# PGTN021_octasource2a_controls.net
KiCad netlist of a schematic drawn in EAGLE
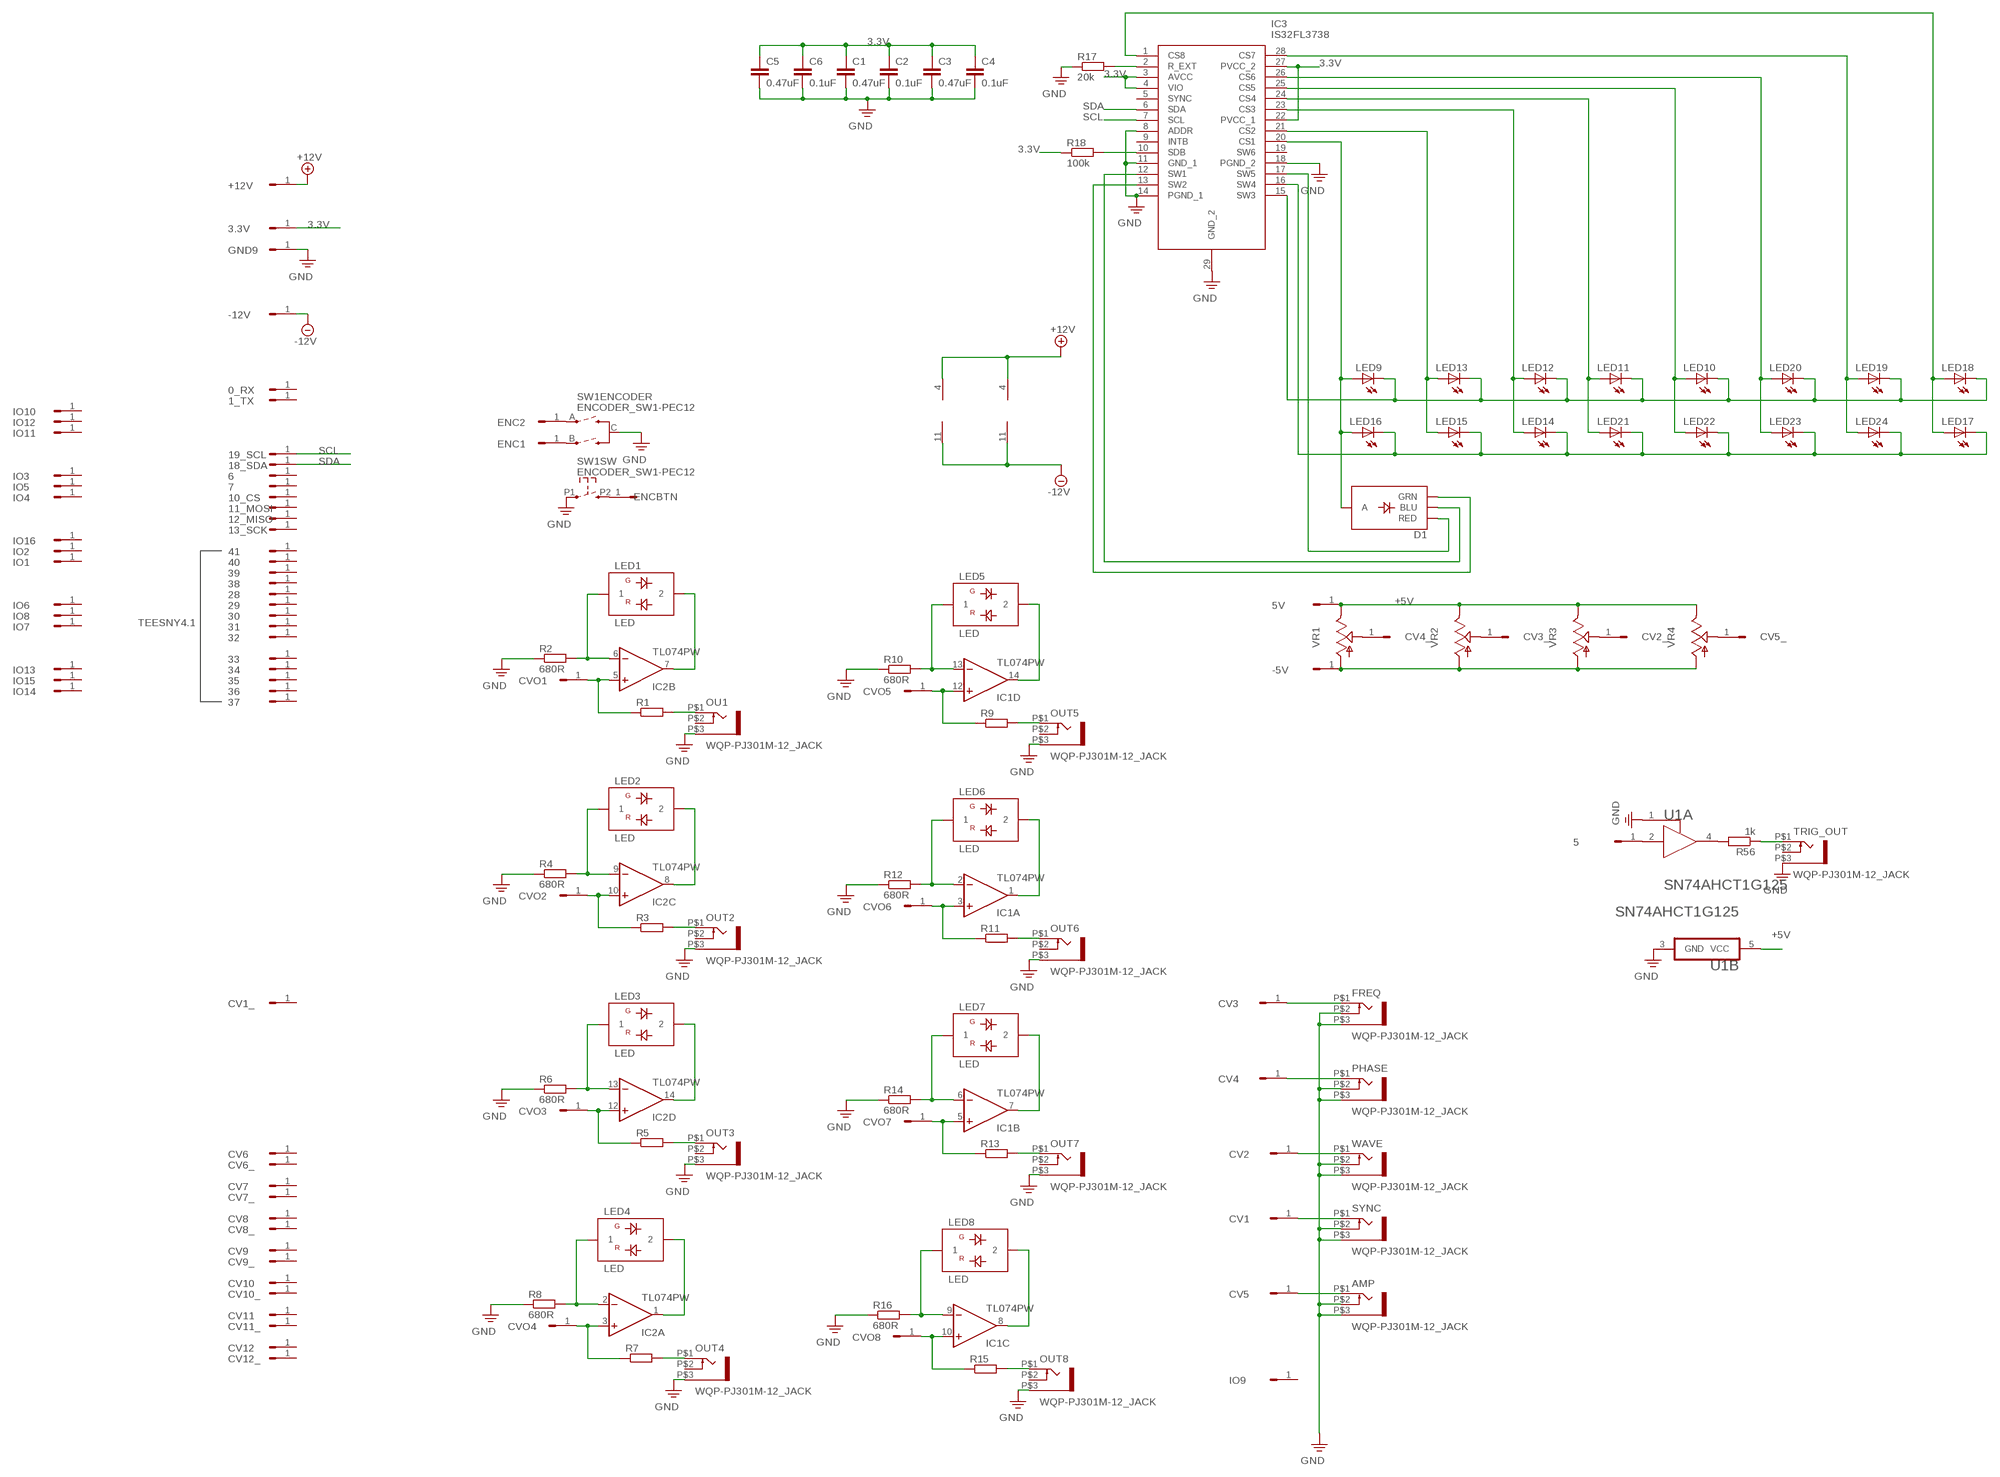
[diagram p0: schematic, sheet 1]

(export (version "E")
  (design (tool "Eeschema 10.0.6"))
  (components
    (comp (ref "+12V")
      (value "HEADER/MALE/01")
      (footprint "eagle-import:HEADER_MALE_01")
      (fields (field (name "SPICEPREFIX") "X"))
      (libsource (lib "eagle-import") (part "HEADER/MALE/01"))
    )
    (comp (ref "-5V")
      (value "HEADER/MALE/01")
      (footprint "eagle-import:HEADER_MALE_01")
      (fields (field (name "SPICEPREFIX") "X"))
      (libsource (lib "eagle-import") (part "HEADER/MALE/01"))
    )
    (comp (ref "-12V")
      (value "HEADER/MALE/01")
      (footprint "eagle-import:HEADER_MALE_01")
      (fields (field (name "SPICEPREFIX") "X"))
      (libsource (lib "eagle-import") (part "HEADER/MALE/01"))
    )
    (comp (ref "0_RX")
      (value "HEADER/MALE/01")
      (footprint "eagle-import:HEADER_MALE_01")
      (fields (field (name "SPICEPREFIX") "X"))
      (libsource (lib "eagle-import") (part "HEADER/MALE/01"))
    )
    (comp (ref "1_TX")
      (value "HEADER/MALE/01")
      (footprint "eagle-import:HEADER_MALE_01")
      (fields (field (name "SPICEPREFIX") "X"))
      (libsource (lib "eagle-import") (part "HEADER/MALE/01"))
    )
    (comp (ref "3.3V")
      (value "HEADER/MALE/01")
      (footprint "eagle-import:HEADER_MALE_01")
      (fields (field (name "SPICEPREFIX") "X"))
      (libsource (lib "eagle-import") (part "HEADER/MALE/01"))
    )
    (comp (ref "5")
      (value "HEADER/MALE/01")
      (footprint "eagle-import:HEADER_MALE_01")
      (fields (field (name "SPICEPREFIX") "X"))
      (libsource (lib "eagle-import") (part "HEADER/MALE/01"))
    )
    (comp (ref "5V")
      (value "HEADER/MALE/01")
      (footprint "eagle-import:HEADER_MALE_01")
      (fields (field (name "SPICEPREFIX") "X"))
      (libsource (lib "eagle-import") (part "HEADER/MALE/01"))
    )
    (comp (ref "6")
      (value "HEADER/MALE/01")
      (footprint "eagle-import:HEADER_MALE_01")
      (fields (field (name "SPICEPREFIX") "X"))
      (libsource (lib "eagle-import") (part "HEADER/MALE/01"))
    )
    (comp (ref "7")
      (value "HEADER/MALE/01")
      (footprint "eagle-import:HEADER_MALE_01")
      (fields (field (name "SPICEPREFIX") "X"))
      (libsource (lib "eagle-import") (part "HEADER/MALE/01"))
    )
    (comp (ref "10_CS")
      (value "HEADER/MALE/01")
      (footprint "eagle-import:HEADER_MALE_01")
      (fields (field (name "SPICEPREFIX") "X"))
      (libsource (lib "eagle-import") (part "HEADER/MALE/01"))
    )
    (comp (ref "11_MOSI")
      (value "HEADER/MALE/01")
      (footprint "eagle-import:HEADER_MALE_01")
      (fields (field (name "SPICEPREFIX") "X"))
      (libsource (lib "eagle-import") (part "HEADER/MALE/01"))
    )
    (comp (ref "12_MISO")
      (value "HEADER/MALE/01")
      (footprint "eagle-import:HEADER_MALE_01")
      (fields (field (name "SPICEPREFIX") "X"))
      (libsource (lib "eagle-import") (part "HEADER/MALE/01"))
    )
    (comp (ref "13_SCK")
      (value "HEADER/MALE/01")
      (footprint "eagle-import:HEADER_MALE_01")
      (fields (field (name "SPICEPREFIX") "X"))
      (libsource (lib "eagle-import") (part "HEADER/MALE/01"))
    )
    (comp (ref "18_SDA")
      (value "HEADER/MALE/01")
      (footprint "eagle-import:HEADER_MALE_01")
      (fields (field (name "SPICEPREFIX") "X"))
      (libsource (lib "eagle-import") (part "HEADER/MALE/01"))
    )
    (comp (ref "19_SCL")
      (value "HEADER/MALE/01")
      (footprint "eagle-import:HEADER_MALE_01")
      (fields (field (name "SPICEPREFIX") "X"))
      (libsource (lib "eagle-import") (part "HEADER/MALE/01"))
    )
    (comp (ref "28")
      (value "HEADER/MALE/01")
      (footprint "eagle-import:HEADER_MALE_01")
      (fields (field (name "SPICEPREFIX") "X"))
      (libsource (lib "eagle-import") (part "HEADER/MALE/01"))
    )
    (comp (ref "29")
      (value "HEADER/MALE/01")
      (footprint "eagle-import:HEADER_MALE_01")
      (fields (field (name "SPICEPREFIX") "X"))
      (libsource (lib "eagle-import") (part "HEADER/MALE/01"))
    )
    (comp (ref "30")
      (value "HEADER/MALE/01")
      (footprint "eagle-import:HEADER_MALE_01")
      (fields (field (name "SPICEPREFIX") "X"))
      (libsource (lib "eagle-import") (part "HEADER/MALE/01"))
    )
    (comp (ref "31")
      (value "HEADER/MALE/01")
      (footprint "eagle-import:HEADER_MALE_01")
      (fields (field (name "SPICEPREFIX") "X"))
      (libsource (lib "eagle-import") (part "HEADER/MALE/01"))
    )
    (comp (ref "32")
      (value "HEADER/MALE/01")
      (footprint "eagle-import:HEADER_MALE_01")
      (fields (field (name "SPICEPREFIX") "X"))
      (libsource (lib "eagle-import") (part "HEADER/MALE/01"))
    )
    (comp (ref "33")
      (value "HEADER/MALE/01")
      (footprint "eagle-import:HEADER_MALE_01")
      (fields (field (name "SPICEPREFIX") "X"))
      (libsource (lib "eagle-import") (part "HEADER/MALE/01"))
    )
    (comp (ref "34")
      (value "HEADER/MALE/01")
      (footprint "eagle-import:HEADER_MALE_01")
      (fields (field (name "SPICEPREFIX") "X"))
      (libsource (lib "eagle-import") (part "HEADER/MALE/01"))
    )
    (comp (ref "35")
      (value "HEADER/MALE/01")
      (footprint "eagle-import:HEADER_MALE_01")
      (fields (field (name "SPICEPREFIX") "X"))
      (libsource (lib "eagle-import") (part "HEADER/MALE/01"))
    )
    (comp (ref "36")
      (value "HEADER/MALE/01")
      (footprint "eagle-import:HEADER_MALE_01")
      (fields (field (name "SPICEPREFIX") "X"))
      (libsource (lib "eagle-import") (part "HEADER/MALE/01"))
    )
    (comp (ref "37")
      (value "HEADER/MALE/01")
      (footprint "eagle-import:HEADER_MALE_01")
      (fields (field (name "SPICEPREFIX") "X"))
      (libsource (lib "eagle-import") (part "HEADER/MALE/01"))
    )
    (comp (ref "38")
      (value "HEADER/MALE/01")
      (footprint "eagle-import:HEADER_MALE_01")
      (fields (field (name "SPICEPREFIX") "X"))
      (libsource (lib "eagle-import") (part "HEADER/MALE/01"))
    )
    (comp (ref "39")
      (value "HEADER/MALE/01")
      (footprint "eagle-import:HEADER_MALE_01")
      (fields (field (name "SPICEPREFIX") "X"))
      (libsource (lib "eagle-import") (part "HEADER/MALE/01"))
    )
    (comp (ref "40")
      (value "HEADER/MALE/01")
      (footprint "eagle-import:HEADER_MALE_01")
      (fields (field (name "SPICEPREFIX") "X"))
      (libsource (lib "eagle-import") (part "HEADER/MALE/01"))
    )
    (comp (ref "41")
      (value "HEADER/MALE/01")
      (footprint "eagle-import:HEADER_MALE_01")
      (fields (field (name "SPICEPREFIX") "X"))
      (libsource (lib "eagle-import") (part "HEADER/MALE/01"))
    )
    (comp (ref "AMP")
      (value "WQP-PJ301M-12_JACK")
      (footprint "eagle-import:WQP-PJ301M-12_JACK")
      (libsource (lib "eagle-import") (part "WQP-PJ301M-12_JACK"))
    )
    (comp (ref "C1")
      (value "0.47uF")
      (footprint "eagle-import:C0603")
      (libsource (lib "eagle-import") (part "CAPACITORC0603"))
    )
    (comp (ref "C2")
      (value "0.1uF")
      (footprint "eagle-import:C0603")
      (libsource (lib "eagle-import") (part "CAPACITORC0603"))
    )
    (comp (ref "C3")
      (value "0.47uF")
      (footprint "eagle-import:C0603")
      (libsource (lib "eagle-import") (part "CAPACITORC0603"))
    )
    (comp (ref "C4")
      (value "0.1uF")
      (footprint "eagle-import:C0603")
      (libsource (lib "eagle-import") (part "CAPACITORC0603"))
    )
    (comp (ref "C5")
      (value "0.47uF")
      (footprint "eagle-import:C0603")
      (libsource (lib "eagle-import") (part "CAPACITORC0603"))
    )
    (comp (ref "C6")
      (value "0.1uF")
      (footprint "eagle-import:C0603")
      (libsource (lib "eagle-import") (part "CAPACITORC0603"))
    )
    (comp (ref "CV1")
      (value "HEADER/MALE/01")
      (footprint "eagle-import:HEADER_MALE_01")
      (fields (field (name "SPICEPREFIX") "X"))
      (libsource (lib "eagle-import") (part "HEADER/MALE/01"))
    )
    (comp (ref "CV1_")
      (value "HEADER/MALE/01")
      (footprint "eagle-import:HEADER_MALE_01")
      (fields (field (name "SPICEPREFIX") "X"))
      (libsource (lib "eagle-import") (part "HEADER/MALE/01"))
    )
    (comp (ref "CV2")
      (value "HEADER/MALE/01")
      (footprint "eagle-import:HEADER_MALE_01")
      (fields (field (name "SPICEPREFIX") "X"))
      (libsource (lib "eagle-import") (part "HEADER/MALE/01"))
    )
    (comp (ref "CV2_")
      (value "HEADER/MALE/01")
      (footprint "eagle-import:HEADER_MALE_01")
      (fields (field (name "SPICEPREFIX") "X"))
      (libsource (lib "eagle-import") (part "HEADER/MALE/01"))
    )
    (comp (ref "CV3")
      (value "HEADER/MALE/01")
      (footprint "eagle-import:HEADER_MALE_01")
      (fields (field (name "SPICEPREFIX") "X"))
      (libsource (lib "eagle-import") (part "HEADER/MALE/01"))
    )
    (comp (ref "CV3_")
      (value "HEADER/MALE/01")
      (footprint "eagle-import:HEADER_MALE_01")
      (fields (field (name "SPICEPREFIX") "X"))
      (libsource (lib "eagle-import") (part "HEADER/MALE/01"))
    )
    (comp (ref "CV4")
      (value "HEADER/MALE/01")
      (footprint "eagle-import:HEADER_MALE_01")
      (fields (field (name "SPICEPREFIX") "X"))
      (libsource (lib "eagle-import") (part "HEADER/MALE/01"))
    )
    (comp (ref "CV4_")
      (value "HEADER/MALE/01")
      (footprint "eagle-import:HEADER_MALE_01")
      (fields (field (name "SPICEPREFIX") "X"))
      (libsource (lib "eagle-import") (part "HEADER/MALE/01"))
    )
    (comp (ref "CV5")
      (value "HEADER/MALE/01")
      (footprint "eagle-import:HEADER_MALE_01")
      (fields (field (name "SPICEPREFIX") "X"))
      (libsource (lib "eagle-import") (part "HEADER/MALE/01"))
    )
    (comp (ref "CV5_")
      (value "HEADER/MALE/01")
      (footprint "eagle-import:HEADER_MALE_01")
      (fields (field (name "SPICEPREFIX") "X"))
      (libsource (lib "eagle-import") (part "HEADER/MALE/01"))
    )
    (comp (ref "CV6")
      (value "HEADER/MALE/01")
      (footprint "eagle-import:HEADER_MALE_01")
      (fields (field (name "SPICEPREFIX") "X"))
      (libsource (lib "eagle-import") (part "HEADER/MALE/01"))
    )
    (comp (ref "CV6_")
      (value "HEADER/MALE/01")
      (footprint "eagle-import:HEADER_MALE_01")
      (fields (field (name "SPICEPREFIX") "X"))
      (libsource (lib "eagle-import") (part "HEADER/MALE/01"))
    )
    (comp (ref "CV7")
      (value "HEADER/MALE/01")
      (footprint "eagle-import:HEADER_MALE_01")
      (fields (field (name "SPICEPREFIX") "X"))
      (libsource (lib "eagle-import") (part "HEADER/MALE/01"))
    )
    (comp (ref "CV7_")
      (value "HEADER/MALE/01")
      (footprint "eagle-import:HEADER_MALE_01")
      (fields (field (name "SPICEPREFIX") "X"))
      (libsource (lib "eagle-import") (part "HEADER/MALE/01"))
    )
    (comp (ref "CV8")
      (value "HEADER/MALE/01")
      (footprint "eagle-import:HEADER_MALE_01")
      (fields (field (name "SPICEPREFIX") "X"))
      (libsource (lib "eagle-import") (part "HEADER/MALE/01"))
    )
    (comp (ref "CV8_")
      (value "HEADER/MALE/01")
      (footprint "eagle-import:HEADER_MALE_01")
      (fields (field (name "SPICEPREFIX") "X"))
      (libsource (lib "eagle-import") (part "HEADER/MALE/01"))
    )
    (comp (ref "CV9")
      (value "HEADER/MALE/01")
      (footprint "eagle-import:HEADER_MALE_01")
      (fields (field (name "SPICEPREFIX") "X"))
      (libsource (lib "eagle-import") (part "HEADER/MALE/01"))
    )
    (comp (ref "CV9_")
      (value "HEADER/MALE/01")
      (footprint "eagle-import:HEADER_MALE_01")
      (fields (field (name "SPICEPREFIX") "X"))
      (libsource (lib "eagle-import") (part "HEADER/MALE/01"))
    )
    (comp (ref "CV10")
      (value "HEADER/MALE/01")
      (footprint "eagle-import:HEADER_MALE_01")
      (fields (field (name "SPICEPREFIX") "X"))
      (libsource (lib "eagle-import") (part "HEADER/MALE/01"))
    )
    (comp (ref "CV10_")
      (value "HEADER/MALE/01")
      (footprint "eagle-import:HEADER_MALE_01")
      (fields (field (name "SPICEPREFIX") "X"))
      (libsource (lib "eagle-import") (part "HEADER/MALE/01"))
    )
    (comp (ref "CV11")
      (value "HEADER/MALE/01")
      (footprint "eagle-import:HEADER_MALE_01")
      (fields (field (name "SPICEPREFIX") "X"))
      (libsource (lib "eagle-import") (part "HEADER/MALE/01"))
    )
    (comp (ref "CV11_")
      (value "HEADER/MALE/01")
      (footprint "eagle-import:HEADER_MALE_01")
      (fields (field (name "SPICEPREFIX") "X"))
      (libsource (lib "eagle-import") (part "HEADER/MALE/01"))
    )
    (comp (ref "CV12")
      (value "HEADER/MALE/01")
      (footprint "eagle-import:HEADER_MALE_01")
      (fields (field (name "SPICEPREFIX") "X"))
      (libsource (lib "eagle-import") (part "HEADER/MALE/01"))
    )
    (comp (ref "CV12_")
      (value "HEADER/MALE/01")
      (footprint "eagle-import:HEADER_MALE_01")
      (fields (field (name "SPICEPREFIX") "X"))
      (libsource (lib "eagle-import") (part "HEADER/MALE/01"))
    )
    (comp (ref "CVO1")
      (value "HEADER/MALE/01")
      (footprint "eagle-import:HEADER_MALE_01")
      (fields (field (name "SPICEPREFIX") "X"))
      (libsource (lib "eagle-import") (part "HEADER/MALE/01"))
    )
    (comp (ref "CVO2")
      (value "HEADER/MALE/01")
      (footprint "eagle-import:HEADER_MALE_01")
      (fields (field (name "SPICEPREFIX") "X"))
      (libsource (lib "eagle-import") (part "HEADER/MALE/01"))
    )
    (comp (ref "CVO3")
      (value "HEADER/MALE/01")
      (footprint "eagle-import:HEADER_MALE_01")
      (fields (field (name "SPICEPREFIX") "X"))
      (libsource (lib "eagle-import") (part "HEADER/MALE/01"))
    )
    (comp (ref "CVO4")
      (value "HEADER/MALE/01")
      (footprint "eagle-import:HEADER_MALE_01")
      (fields (field (name "SPICEPREFIX") "X"))
      (libsource (lib "eagle-import") (part "HEADER/MALE/01"))
    )
    (comp (ref "CVO5")
      (value "HEADER/MALE/01")
      (footprint "eagle-import:HEADER_MALE_01")
      (fields (field (name "SPICEPREFIX") "X"))
      (libsource (lib "eagle-import") (part "HEADER/MALE/01"))
    )
    (comp (ref "CVO6")
      (value "HEADER/MALE/01")
      (footprint "eagle-import:HEADER_MALE_01")
      (fields (field (name "SPICEPREFIX") "X"))
      (libsource (lib "eagle-import") (part "HEADER/MALE/01"))
    )
    (comp (ref "CVO7")
      (value "HEADER/MALE/01")
      (footprint "eagle-import:HEADER_MALE_01")
      (fields (field (name "SPICEPREFIX") "X"))
      (libsource (lib "eagle-import") (part "HEADER/MALE/01"))
    )
    (comp (ref "CVO8")
      (value "HEADER/MALE/01")
      (footprint "eagle-import:HEADER_MALE_01")
      (fields (field (name "SPICEPREFIX") "X"))
      (libsource (lib "eagle-import") (part "HEADER/MALE/01"))
    )
    (comp (ref "D1")
      (value "LED-RGB-CADIALIGHT1210")
      (footprint "eagle-import:CHIPLED_1210")
      (libsource (lib "eagle-import") (part "LED-RGB-CADIALIGHT1210"))
    )
    (comp (ref "ENC1")
      (value "HEADER/MALE/01")
      (footprint "eagle-import:HEADER_MALE_01")
      (fields (field (name "SPICEPREFIX") "X"))
      (libsource (lib "eagle-import") (part "HEADER/MALE/01"))
    )
    (comp (ref "ENC2")
      (value "HEADER/MALE/01")
      (footprint "eagle-import:HEADER_MALE_01")
      (fields (field (name "SPICEPREFIX") "X"))
      (libsource (lib "eagle-import") (part "HEADER/MALE/01"))
    )
    (comp (ref "ENCBTN")
      (value "HEADER/MALE/01")
      (footprint "eagle-import:HEADER_MALE_01")
      (fields (field (name "SPICEPREFIX") "X"))
      (libsource (lib "eagle-import") (part "HEADER/MALE/01"))
    )
    (comp (ref "FREQ")
      (value "WQP-PJ301M-12_JACK")
      (footprint "eagle-import:WQP-PJ301M-12_JACK")
      (libsource (lib "eagle-import") (part "WQP-PJ301M-12_JACK"))
    )
    (comp (ref "GND9")
      (value "HEADER/MALE/01")
      (footprint "eagle-import:HEADER_MALE_01")
      (fields (field (name "SPICEPREFIX") "X"))
      (libsource (lib "eagle-import") (part "HEADER/MALE/01"))
    )
    (comp (ref "IC1")
      (value "TL074PW")
      (footprint "eagle-import:TSSOP14")
      (libsource (lib "eagle-import") (part "TL074PW"))
    )
    (comp (ref "IC2")
      (value "TL074PW")
      (footprint "eagle-import:TSSOP14")
      (libsource (lib "eagle-import") (part "TL074PW"))
    )
    (comp (ref "IC3")
      (value "IS32FL3738")
      (footprint "eagle-import:TSSOP29")
      (fields (field (name "MANUFACTURER_PART_NUMBER") "IS32FL3738-ZLA3-TR"))
      (libsource (lib "eagle-import") (part "IS32FL3738"))
    )
    (comp (ref "IO1")
      (value "HEADER/MALE/01")
      (footprint "eagle-import:HEADER_MALE_01")
      (fields (field (name "SPICEPREFIX") "X"))
      (libsource (lib "eagle-import") (part "HEADER/MALE/01"))
    )
    (comp (ref "IO2")
      (value "HEADER/MALE/01")
      (footprint "eagle-import:HEADER_MALE_01")
      (fields (field (name "SPICEPREFIX") "X"))
      (libsource (lib "eagle-import") (part "HEADER/MALE/01"))
    )
    (comp (ref "IO3")
      (value "HEADER/MALE/01")
      (footprint "eagle-import:HEADER_MALE_01")
      (fields (field (name "SPICEPREFIX") "X"))
      (libsource (lib "eagle-import") (part "HEADER/MALE/01"))
    )
    (comp (ref "IO4")
      (value "HEADER/MALE/01")
      (footprint "eagle-import:HEADER_MALE_01")
      (fields (field (name "SPICEPREFIX") "X"))
      (libsource (lib "eagle-import") (part "HEADER/MALE/01"))
    )
    (comp (ref "IO5")
      (value "HEADER/MALE/01")
      (footprint "eagle-import:HEADER_MALE_01")
      (fields (field (name "SPICEPREFIX") "X"))
      (libsource (lib "eagle-import") (part "HEADER/MALE/01"))
    )
    (comp (ref "IO6")
      (value "HEADER/MALE/01")
      (footprint "eagle-import:HEADER_MALE_01")
      (fields (field (name "SPICEPREFIX") "X"))
      (libsource (lib "eagle-import") (part "HEADER/MALE/01"))
    )
    (comp (ref "IO7")
      (value "HEADER/MALE/01")
      (footprint "eagle-import:HEADER_MALE_01")
      (fields (field (name "SPICEPREFIX") "X"))
      (libsource (lib "eagle-import") (part "HEADER/MALE/01"))
    )
    (comp (ref "IO8")
      (value "HEADER/MALE/01")
      (footprint "eagle-import:HEADER_MALE_01")
      (fields (field (name "SPICEPREFIX") "X"))
      (libsource (lib "eagle-import") (part "HEADER/MALE/01"))
    )
    (comp (ref "IO9")
      (value "HEADER/MALE/01")
      (footprint "eagle-import:HEADER_MALE_01")
      (fields (field (name "SPICEPREFIX") "X"))
      (libsource (lib "eagle-import") (part "HEADER/MALE/01"))
    )
    (comp (ref "IO10")
      (value "HEADER/MALE/01")
      (footprint "eagle-import:HEADER_MALE_01")
      (fields (field (name "SPICEPREFIX") "X"))
      (libsource (lib "eagle-import") (part "HEADER/MALE/01"))
    )
    (comp (ref "IO11")
      (value "HEADER/MALE/01")
      (footprint "eagle-import:HEADER_MALE_01")
      (fields (field (name "SPICEPREFIX") "X"))
      (libsource (lib "eagle-import") (part "HEADER/MALE/01"))
    )
    (comp (ref "IO12")
      (value "HEADER/MALE/01")
      (footprint "eagle-import:HEADER_MALE_01")
      (fields (field (name "SPICEPREFIX") "X"))
      (libsource (lib "eagle-import") (part "HEADER/MALE/01"))
    )
    (comp (ref "IO13")
      (value "HEADER/MALE/01")
      (footprint "eagle-import:HEADER_MALE_01")
      (fields (field (name "SPICEPREFIX") "X"))
      (libsource (lib "eagle-import") (part "HEADER/MALE/01"))
    )
    (comp (ref "IO14")
      (value "HEADER/MALE/01")
      (footprint "eagle-import:HEADER_MALE_01")
      (fields (field (name "SPICEPREFIX") "X"))
      (libsource (lib "eagle-import") (part "HEADER/MALE/01"))
    )
    (comp (ref "IO15")
      (value "HEADER/MALE/01")
      (footprint "eagle-import:HEADER_MALE_01")
      (fields (field (name "SPICEPREFIX") "X"))
      (libsource (lib "eagle-import") (part "HEADER/MALE/01"))
    )
    (comp (ref "IO16")
      (value "HEADER/MALE/01")
      (footprint "eagle-import:HEADER_MALE_01")
      (fields (field (name "SPICEPREFIX") "X"))
      (libsource (lib "eagle-import") (part "HEADER/MALE/01"))
    )
    (comp (ref "LED1")
      (value "LED")
      (footprint "eagle-import:OG-LEDS_LED3MM")
      (libsource (lib "eagle-import") (part "LED-BICOLOR-SHARED"))
    )
    (comp (ref "LED2")
      (value "LED")
      (footprint "eagle-import:OG-LEDS_LED3MM")
      (libsource (lib "eagle-import") (part "LED-BICOLOR-SHARED"))
    )
    (comp (ref "LED3")
      (value "LED")
      (footprint "eagle-import:OG-LEDS_LED3MM")
      (libsource (lib "eagle-import") (part "LED-BICOLOR-SHARED"))
    )
    (comp (ref "LED4")
      (value "LED")
      (footprint "eagle-import:OG-LEDS_LED3MM")
      (libsource (lib "eagle-import") (part "LED-BICOLOR-SHARED"))
    )
    (comp (ref "LED5")
      (value "LED")
      (footprint "eagle-import:OG-LEDS_LED3MM")
      (libsource (lib "eagle-import") (part "LED-BICOLOR-SHARED"))
    )
    (comp (ref "LED6")
      (value "LED")
      (footprint "eagle-import:OG-LEDS_LED3MM")
      (libsource (lib "eagle-import") (part "LED-BICOLOR-SHARED"))
    )
    (comp (ref "LED7")
      (value "LED")
      (footprint "eagle-import:OG-LEDS_LED3MM")
      (libsource (lib "eagle-import") (part "LED-BICOLOR-SHARED"))
    )
    (comp (ref "LED8")
      (value "LED")
      (footprint "eagle-import:OG-LEDS_LED3MM")
      (libsource (lib "eagle-import") (part "LED-BICOLOR-SHARED"))
    )
    (comp (ref "LED9")
      (value "LEDCHIPLED_0805")
      (footprint "eagle-import:CHIPLED_0805")
      (libsource (lib "eagle-import") (part "LEDCHIPLED_0805"))
    )
    (comp (ref "LED10")
      (value "LEDCHIPLED_0805")
      (footprint "eagle-import:CHIPLED_0805")
      (libsource (lib "eagle-import") (part "LEDCHIPLED_0805"))
    )
    (comp (ref "LED11")
      (value "LEDCHIPLED_0805")
      (footprint "eagle-import:CHIPLED_0805")
      (libsource (lib "eagle-import") (part "LEDCHIPLED_0805"))
    )
    (comp (ref "LED12")
      (value "LEDCHIPLED_0805")
      (footprint "eagle-import:CHIPLED_0805")
      (libsource (lib "eagle-import") (part "LEDCHIPLED_0805"))
    )
    (comp (ref "LED13")
      (value "LEDCHIPLED_0805")
      (footprint "eagle-import:CHIPLED_0805")
      (libsource (lib "eagle-import") (part "LEDCHIPLED_0805"))
    )
    (comp (ref "LED14")
      (value "LEDCHIPLED_0805")
      (footprint "eagle-import:CHIPLED_0805")
      (libsource (lib "eagle-import") (part "LEDCHIPLED_0805"))
    )
    (comp (ref "LED15")
      (value "LEDCHIPLED_0805")
      (footprint "eagle-import:CHIPLED_0805")
      (libsource (lib "eagle-import") (part "LEDCHIPLED_0805"))
    )
    (comp (ref "LED16")
      (value "LEDCHIPLED_0805")
      (footprint "eagle-import:CHIPLED_0805")
      (libsource (lib "eagle-import") (part "LEDCHIPLED_0805"))
    )
    (comp (ref "LED17")
      (value "LEDCHIPLED_0805")
      (footprint "eagle-import:CHIPLED_0805")
      (libsource (lib "eagle-import") (part "LEDCHIPLED_0805"))
    )
    (comp (ref "LED18")
      (value "LEDCHIPLED_0805")
      (footprint "eagle-import:CHIPLED_0805")
      (libsource (lib "eagle-import") (part "LEDCHIPLED_0805"))
    )
    (comp (ref "LED19")
      (value "LEDCHIPLED_0805")
      (footprint "eagle-import:CHIPLED_0805")
      (libsource (lib "eagle-import") (part "LEDCHIPLED_0805"))
    )
    (comp (ref "LED20")
      (value "LEDCHIPLED_0805")
      (footprint "eagle-import:CHIPLED_0805")
      (libsource (lib "eagle-import") (part "LEDCHIPLED_0805"))
    )
    (comp (ref "LED21")
      (value "LEDCHIPLED_0805")
      (footprint "eagle-import:CHIPLED_0805")
      (libsource (lib "eagle-import") (part "LEDCHIPLED_0805"))
    )
    (comp (ref "LED22")
      (value "LEDCHIPLED_0805")
      (footprint "eagle-import:CHIPLED_0805")
      (libsource (lib "eagle-import") (part "LEDCHIPLED_0805"))
    )
    (comp (ref "LED23")
      (value "LEDCHIPLED_0805")
      (footprint "eagle-import:CHIPLED_0805")
      (libsource (lib "eagle-import") (part "LEDCHIPLED_0805"))
    )
    (comp (ref "LED24")
      (value "LEDCHIPLED_0805")
      (footprint "eagle-import:CHIPLED_0805")
      (libsource (lib "eagle-import") (part "LEDCHIPLED_0805"))
    )
    (comp (ref "OU1")
      (value "WQP-PJ301M-12_JACK")
      (footprint "eagle-import:WQP-PJ301M-12_JACK")
      (libsource (lib "eagle-import") (part "WQP-PJ301M-12_JACK"))
    )
    (comp (ref "OUT2")
      (value "WQP-PJ301M-12_JACK")
      (footprint "eagle-import:WQP-PJ301M-12_JACK")
      (libsource (lib "eagle-import") (part "WQP-PJ301M-12_JACK"))
    )
    (comp (ref "OUT3")
      (value "WQP-PJ301M-12_JACK")
      (footprint "eagle-import:WQP-PJ301M-12_JACK")
      (libsource (lib "eagle-import") (part "WQP-PJ301M-12_JACK"))
    )
    (comp (ref "OUT4")
      (value "WQP-PJ301M-12_JACK")
      (footprint "eagle-import:WQP-PJ301M-12_JACK")
      (libsource (lib "eagle-import") (part "WQP-PJ301M-12_JACK"))
    )
    (comp (ref "OUT5")
      (value "WQP-PJ301M-12_JACK")
      (footprint "eagle-import:WQP-PJ301M-12_JACK")
      (libsource (lib "eagle-import") (part "WQP-PJ301M-12_JACK"))
    )
    (comp (ref "OUT6")
      (value "WQP-PJ301M-12_JACK")
      (footprint "eagle-import:WQP-PJ301M-12_JACK")
      (libsource (lib "eagle-import") (part "WQP-PJ301M-12_JACK"))
    )
    (comp (ref "OUT7")
      (value "WQP-PJ301M-12_JACK")
      (footprint "eagle-import:WQP-PJ301M-12_JACK")
      (libsource (lib "eagle-import") (part "WQP-PJ301M-12_JACK"))
    )
    (comp (ref "OUT8")
      (value "WQP-PJ301M-12_JACK")
      (footprint "eagle-import:WQP-PJ301M-12_JACK")
      (libsource (lib "eagle-import") (part "WQP-PJ301M-12_JACK"))
    )
    (comp (ref "PHASE")
      (value "WQP-PJ301M-12_JACK")
      (footprint "eagle-import:WQP-PJ301M-12_JACK")
      (libsource (lib "eagle-import") (part "WQP-PJ301M-12_JACK"))
    )
    (comp (ref "R1")
      (value "RESISTOR")
      (footprint "eagle-import:R0603")
      (libsource (lib "eagle-import") (part "RESISTOR"))
    )
    (comp (ref "R2")
      (value "680R")
      (footprint "eagle-import:R0603")
      (libsource (lib "eagle-import") (part "RESISTOR"))
    )
    (comp (ref "R3")
      (value "RESISTOR")
      (footprint "eagle-import:R0603")
      (libsource (lib "eagle-import") (part "RESISTOR"))
    )
    (comp (ref "R4")
      (value "680R")
      (footprint "eagle-import:R0603")
      (libsource (lib "eagle-import") (part "RESISTOR"))
    )
    (comp (ref "R5")
      (value "RESISTOR")
      (footprint "eagle-import:R0603")
      (libsource (lib "eagle-import") (part "RESISTOR"))
    )
    (comp (ref "R6")
      (value "680R")
      (footprint "eagle-import:R0603")
      (libsource (lib "eagle-import") (part "RESISTOR"))
    )
    (comp (ref "R7")
      (value "RESISTOR")
      (footprint "eagle-import:R0603")
      (libsource (lib "eagle-import") (part "RESISTOR"))
    )
    (comp (ref "R8")
      (value "680R")
      (footprint "eagle-import:R0603")
      (libsource (lib "eagle-import") (part "RESISTOR"))
    )
    (comp (ref "R9")
      (value "RESISTOR")
      (footprint "eagle-import:R0603")
      (libsource (lib "eagle-import") (part "RESISTOR"))
    )
    (comp (ref "R10")
      (value "680R")
      (footprint "eagle-import:R0603")
      (libsource (lib "eagle-import") (part "RESISTOR"))
    )
    (comp (ref "R11")
      (value "RESISTOR")
      (footprint "eagle-import:R0603")
      (libsource (lib "eagle-import") (part "RESISTOR"))
    )
    (comp (ref "R12")
      (value "680R")
      (footprint "eagle-import:R0603")
      (libsource (lib "eagle-import") (part "RESISTOR"))
    )
    (comp (ref "R13")
      (value "RESISTOR")
      (footprint "eagle-import:R0603")
      (libsource (lib "eagle-import") (part "RESISTOR"))
    )
    (comp (ref "R14")
      (value "680R")
      (footprint "eagle-import:R0603")
      (libsource (lib "eagle-import") (part "RESISTOR"))
    )
    (comp (ref "R15")
      (value "RESISTOR")
      (footprint "eagle-import:R0603")
      (libsource (lib "eagle-import") (part "RESISTOR"))
    )
    (comp (ref "R16")
      (value "680R")
      (footprint "eagle-import:R0603")
      (libsource (lib "eagle-import") (part "RESISTOR"))
    )
    (comp (ref "R17")
      (value "20k")
      (footprint "eagle-import:R0603")
      (libsource (lib "eagle-import") (part "RESISTOR"))
    )
    (comp (ref "R18")
      (value "100k")
      (footprint "eagle-import:R0603")
      (libsource (lib "eagle-import") (part "RESISTOR"))
    )
    (comp (ref "R56")
      (value "1k")
      (footprint "eagle-import:R0603")
      (libsource (lib "eagle-import") (part "RESISTOR"))
    )
    (comp (ref "SW1")
      (value "ENCODER_SW1-PEC12")
      (footprint "eagle-import:PEC12_INCREMENTAL_ENCODER")
      (libsource (lib "eagle-import") (part "ENCODER_SW1-PEC12"))
    )
    (comp (ref "SYNC")
      (value "WQP-PJ301M-12_JACK")
      (footprint "eagle-import:WQP-PJ301M-12_JACK")
      (libsource (lib "eagle-import") (part "WQP-PJ301M-12_JACK"))
    )
    (comp (ref "TRIG_OUT")
      (value "WQP-PJ301M-12_JACK")
      (footprint "eagle-import:WQP-PJ301M-12_JACK")
      (libsource (lib "eagle-import") (part "WQP-PJ301M-12_JACK"))
    )
    (comp (ref "U1")
      (value "74AHCT1G125\"")
      (footprint "eagle-import:74AHCT1G125")
      (fields (field (name "MF") "Texas Instruments") (field (name "MPN") "SN74AHCT1G125"))
      (libsource (lib "eagle-import") (part "74AHCT1G125{dblquote}"))
    )
    (comp (ref "VR1")
      (value "9MM_SNAP-IN_POT_")
      (footprint "eagle-import:9MM_SNAP-IN_POT")
      (libsource (lib "eagle-import") (part "9MM_SNAP-IN_POT_"))
    )
    (comp (ref "VR2")
      (value "9MM_SNAP-IN_POT_")
      (footprint "eagle-import:9MM_SNAP-IN_POT")
      (libsource (lib "eagle-import") (part "9MM_SNAP-IN_POT_"))
    )
    (comp (ref "VR3")
      (value "9MM_SNAP-IN_POT_")
      (footprint "eagle-import:9MM_SNAP-IN_POT")
      (libsource (lib "eagle-import") (part "9MM_SNAP-IN_POT_"))
    )
    (comp (ref "VR4")
      (value "9MM_SNAP-IN_POT_")
      (footprint "eagle-import:9MM_SNAP-IN_POT")
      (libsource (lib "eagle-import") (part "9MM_SNAP-IN_POT_"))
    )
    (comp (ref "WAVE")
      (value "WQP-PJ301M-12_JACK")
      (footprint "eagle-import:WQP-PJ301M-12_JACK")
      (libsource (lib "eagle-import") (part "WQP-PJ301M-12_JACK"))
    )
  )
  (nets
    (net (code "1") (name "+12V") (class "Default")
      (node (ref "+12V") (pin "1") (pinfunction "3_1") (pintype "passive"))
      (node (ref "IC1") (pin "4") (pinfunction "V+_4") (pintype "power_in"))
      (node (ref "IC2") (pin "4") (pinfunction "V+_4") (pintype "power_in"))
    )
    (net (code "2") (name "-12V") (class "Default")
      (node (ref "-12V") (pin "1") (pinfunction "3_1") (pintype "passive"))
      (node (ref "IC1") (pin "11") (pinfunction "V-_11") (pintype "power_in"))
      (node (ref "IC2") (pin "11") (pinfunction "V-_11") (pintype "power_in"))
    )
    (net (code "3") (name "/+5V") (class "Default")
      (node (ref "5V") (pin "1") (pinfunction "3_1") (pintype "passive"))
      (node (ref "U1") (pin "5") (pinfunction "VCC_5") (pintype "power_in"))
      (node (ref "VR1") (pin "3") (pinfunction "E_3") (pintype "passive"))
      (node (ref "VR2") (pin "3") (pinfunction "E_3") (pintype "passive"))
      (node (ref "VR3") (pin "3") (pinfunction "E_3") (pintype "passive"))
      (node (ref "VR4") (pin "3") (pinfunction "E_3") (pintype "passive"))
    )
    (net (code "4") (name "/3.3V") (class "Default")
      (node (ref "3.3V") (pin "1") (pinfunction "3_1") (pintype "passive"))
      (node (ref "C1") (pin "1") (pinfunction "1_1") (pintype "passive"))
      (node (ref "C2") (pin "1") (pinfunction "1_1") (pintype "passive"))
      (node (ref "C3") (pin "1") (pinfunction "1_1") (pintype "passive"))
      (node (ref "C4") (pin "1") (pinfunction "1_1") (pintype "passive"))
      (node (ref "C5") (pin "1") (pinfunction "1_1") (pintype "passive"))
      (node (ref "C6") (pin "1") (pinfunction "1_1") (pintype "passive"))
      (node (ref "IC3") (pin "22") (pinfunction "PVCC_1_22") (pintype "power_in"))
      (node (ref "IC3") (pin "27") (pinfunction "PVCC_2_27") (pintype "power_in"))
      (node (ref "IC3") (pin "3") (pinfunction "AVCC_3") (pintype "power_in"))
      (node (ref "IC3") (pin "4") (pinfunction "VIO_4") (pintype "input"))
      (node (ref "R18") (pin "1") (pinfunction "1_1") (pintype "passive"))
    )
    (net (code "5") (name "/SCL") (class "Default")
      (node (ref "19_SCL") (pin "1") (pinfunction "3_1") (pintype "passive"))
      (node (ref "IC3") (pin "7") (pinfunction "SCL_7") (pintype "bidirectional"))
    )
    (net (code "6") (name "/SDA") (class "Default")
      (node (ref "18_SDA") (pin "1") (pinfunction "3_1") (pintype "passive"))
      (node (ref "IC3") (pin "6") (pinfunction "SDA_6") (pintype "bidirectional"))
    )
    (net (code "7") (name "GND") (class "Default")
      (node (ref "AMP") (pin "P$2") (pinfunction "3_P$2") (pintype "passive"))
      (node (ref "AMP") (pin "P$3") (pinfunction "1_P$3") (pintype "passive"))
      (node (ref "C1") (pin "2") (pinfunction "2_2") (pintype "passive"))
      (node (ref "C2") (pin "2") (pinfunction "2_2") (pintype "passive"))
      (node (ref "C3") (pin "2") (pinfunction "2_2") (pintype "passive"))
      (node (ref "C4") (pin "2") (pinfunction "2_2") (pintype "passive"))
      (node (ref "C5") (pin "2") (pinfunction "2_2") (pintype "passive"))
      (node (ref "C6") (pin "2") (pinfunction "2_2") (pintype "passive"))
      (node (ref "FREQ") (pin "P$2") (pinfunction "3_P$2") (pintype "passive"))
      (node (ref "FREQ") (pin "P$3") (pinfunction "1_P$3") (pintype "passive"))
      (node (ref "GND9") (pin "1") (pinfunction "3_1") (pintype "passive"))
      (node (ref "IC3") (pin "11") (pinfunction "GND_1_11") (pintype "power_in"))
      (node (ref "IC3") (pin "14") (pinfunction "PGND_1_14") (pintype "power_in"))
      (node (ref "IC3") (pin "18") (pinfunction "PGND_2_18") (pintype "power_in"))
      (node (ref "IC3") (pin "29") (pinfunction "GND_2_29") (pintype "power_in"))
      (node (ref "IC3") (pin "8") (pinfunction "ADDR_8") (pintype "input"))
      (node (ref "OU1") (pin "P$3") (pinfunction "1_P$3") (pintype "passive"))
      (node (ref "OUT2") (pin "P$3") (pinfunction "1_P$3") (pintype "passive"))
      (node (ref "OUT3") (pin "P$3") (pinfunction "1_P$3") (pintype "passive"))
      (node (ref "OUT4") (pin "P$3") (pinfunction "1_P$3") (pintype "passive"))
      (node (ref "OUT5") (pin "P$3") (pinfunction "1_P$3") (pintype "passive"))
      (node (ref "OUT6") (pin "P$3") (pinfunction "1_P$3") (pintype "passive"))
      (node (ref "OUT7") (pin "P$3") (pinfunction "1_P$3") (pintype "passive"))
      (node (ref "OUT8") (pin "P$3") (pinfunction "1_P$3") (pintype "passive"))
      (node (ref "PHASE") (pin "P$2") (pinfunction "3_P$2") (pintype "passive"))
      (node (ref "PHASE") (pin "P$3") (pinfunction "1_P$3") (pintype "passive"))
      (node (ref "R10") (pin "1") (pinfunction "1_1") (pintype "passive"))
      (node (ref "R12") (pin "1") (pinfunction "1_1") (pintype "passive"))
      (node (ref "R14") (pin "1") (pinfunction "1_1") (pintype "passive"))
      (node (ref "R16") (pin "1") (pinfunction "1_1") (pintype "passive"))
      (node (ref "R17") (pin "1") (pinfunction "1_1") (pintype "passive"))
      (node (ref "R2") (pin "1") (pinfunction "1_1") (pintype "passive"))
      (node (ref "R4") (pin "1") (pinfunction "1_1") (pintype "passive"))
      (node (ref "R6") (pin "1") (pinfunction "1_1") (pintype "passive"))
      (node (ref "R8") (pin "1") (pinfunction "1_1") (pintype "passive"))
      (node (ref "SW1") (pin "C") (pinfunction "C_C") (pintype "passive"))
      (node (ref "SW1") (pin "P1") (pinfunction "1_P1") (pintype "passive"))
      (node (ref "SYNC") (pin "P$2") (pinfunction "3_P$2") (pintype "passive"))
      (node (ref "SYNC") (pin "P$3") (pinfunction "1_P$3") (pintype "passive"))
      (node (ref "TRIG_OUT") (pin "P$3") (pinfunction "1_P$3") (pintype "passive"))
      (node (ref "U1") (pin "1") (pinfunction "~{OE}_1") (pintype "input"))
      (node (ref "U1") (pin "3") (pinfunction "GND_3") (pintype "power_in"))
      (node (ref "WAVE") (pin "P$2") (pinfunction "3_P$2") (pintype "passive"))
      (node (ref "WAVE") (pin "P$3") (pinfunction "1_P$3") (pintype "passive"))
    )
    (net (code "8") (name "Net-(-5V-3)") (class "Default")
      (node (ref "-5V") (pin "1") (pinfunction "3_1") (pintype "passive"))
      (node (ref "VR1") (pin "1") (pinfunction "A_1") (pintype "passive"))
      (node (ref "VR2") (pin "1") (pinfunction "A_1") (pintype "passive"))
      (node (ref "VR3") (pin "1") (pinfunction "A_1") (pintype "passive"))
      (node (ref "VR4") (pin "1") (pinfunction "A_1") (pintype "passive"))
    )
    (net (code "9") (name "Net-(5-3)") (class "Default")
      (node (ref "5") (pin "1") (pinfunction "3_1") (pintype "passive"))
      (node (ref "U1") (pin "2") (pinfunction "A_2") (pintype "input"))
    )
    (net (code "10") (name "Net-(AMP-2)") (class "Default")
      (node (ref "AMP") (pin "P$1") (pinfunction "2_P$1") (pintype "passive"))
      (node (ref "CV5") (pin "1") (pinfunction "3_1") (pintype "passive"))
    )
    (net (code "11") (name "Net-(CV1-3)") (class "Default")
      (node (ref "CV1") (pin "1") (pinfunction "3_1") (pintype "passive"))
      (node (ref "SYNC") (pin "P$1") (pinfunction "2_P$1") (pintype "passive"))
    )
    (net (code "12") (name "Net-(CV2-3)") (class "Default")
      (node (ref "CV2") (pin "1") (pinfunction "3_1") (pintype "passive"))
      (node (ref "WAVE") (pin "P$1") (pinfunction "2_P$1") (pintype "passive"))
    )
    (net (code "13") (name "Net-(CV2_-3)") (class "Default")
      (node (ref "CV2_") (pin "1") (pinfunction "3_1") (pintype "passive"))
      (node (ref "VR3") (pin "2") (pinfunction "S_2") (pintype "passive"))
    )
    (net (code "14") (name "Net-(CV3-3)") (class "Default")
      (node (ref "CV3") (pin "1") (pinfunction "3_1") (pintype "passive"))
      (node (ref "FREQ") (pin "P$1") (pinfunction "2_P$1") (pintype "passive"))
    )
    (net (code "15") (name "Net-(CV3_-3)") (class "Default")
      (node (ref "CV3_") (pin "1") (pinfunction "3_1") (pintype "passive"))
      (node (ref "VR2") (pin "2") (pinfunction "S_2") (pintype "passive"))
    )
    (net (code "16") (name "Net-(CV4-3)") (class "Default")
      (node (ref "CV4") (pin "1") (pinfunction "3_1") (pintype "passive"))
      (node (ref "PHASE") (pin "P$1") (pinfunction "2_P$1") (pintype "passive"))
    )
    (net (code "17") (name "Net-(CV4_-3)") (class "Default")
      (node (ref "CV4_") (pin "1") (pinfunction "3_1") (pintype "passive"))
      (node (ref "VR1") (pin "2") (pinfunction "S_2") (pintype "passive"))
    )
    (net (code "18") (name "Net-(CV5_-3)") (class "Default")
      (node (ref "CV5_") (pin "1") (pinfunction "3_1") (pintype "passive"))
      (node (ref "VR4") (pin "2") (pinfunction "S_2") (pintype "passive"))
    )
    (net (code "19") (name "Net-(CVO1-3)") (class "Default")
      (node (ref "CVO1") (pin "1") (pinfunction "3_1") (pintype "passive"))
      (node (ref "IC2") (pin "5") (pinfunction "+IN_5") (pintype "input"))
      (node (ref "R1") (pin "1") (pinfunction "1_1") (pintype "passive"))
    )
    (net (code "20") (name "Net-(CVO2-3)") (class "Default")
      (node (ref "CVO2") (pin "1") (pinfunction "3_1") (pintype "passive"))
      (node (ref "IC2") (pin "10") (pinfunction "+IN_10") (pintype "input"))
      (node (ref "R3") (pin "1") (pinfunction "1_1") (pintype "passive"))
    )
    (net (code "21") (name "Net-(CVO3-3)") (class "Default")
      (node (ref "CVO3") (pin "1") (pinfunction "3_1") (pintype "passive"))
      (node (ref "IC2") (pin "12") (pinfunction "+IN_12") (pintype "input"))
      (node (ref "R5") (pin "1") (pinfunction "1_1") (pintype "passive"))
    )
    (net (code "22") (name "Net-(CVO4-3)") (class "Default")
      (node (ref "CVO4") (pin "1") (pinfunction "3_1") (pintype "passive"))
      (node (ref "IC2") (pin "3") (pinfunction "+IN_3") (pintype "input"))
      (node (ref "R7") (pin "1") (pinfunction "1_1") (pintype "passive"))
    )
    (net (code "23") (name "Net-(CVO5-3)") (class "Default")
      (node (ref "CVO5") (pin "1") (pinfunction "3_1") (pintype "passive"))
      (node (ref "IC1") (pin "12") (pinfunction "+IN_12") (pintype "input"))
      (node (ref "R9") (pin "1") (pinfunction "1_1") (pintype "passive"))
    )
    (net (code "24") (name "Net-(CVO6-3)") (class "Default")
      (node (ref "CVO6") (pin "1") (pinfunction "3_1") (pintype "passive"))
      (node (ref "IC1") (pin "3") (pinfunction "+IN_3") (pintype "input"))
      (node (ref "R11") (pin "1") (pinfunction "1_1") (pintype "passive"))
    )
    (net (code "25") (name "Net-(CVO7-3)") (class "Default")
      (node (ref "CVO7") (pin "1") (pinfunction "3_1") (pintype "passive"))
      (node (ref "IC1") (pin "5") (pinfunction "+IN_5") (pintype "input"))
      (node (ref "R13") (pin "1") (pinfunction "1_1") (pintype "passive"))
    )
    (net (code "26") (name "Net-(CVO8-3)") (class "Default")
      (node (ref "CVO8") (pin "1") (pinfunction "3_1") (pintype "passive"))
      (node (ref "IC1") (pin "10") (pinfunction "+IN_10") (pintype "input"))
      (node (ref "R15") (pin "1") (pinfunction "1_1") (pintype "passive"))
    )
    (net (code "27") (name "Net-(D1-A)") (class "Default")
      (node (ref "D1") (pin "4") (pinfunction "A_4") (pintype "bidirectional"))
      (node (ref "IC3") (pin "20") (pinfunction "CS1_20") (pintype "output"))
      (node (ref "LED16") (pin "A") (pinfunction "A_A") (pintype "passive"))
      (node (ref "LED9") (pin "A") (pinfunction "A_A") (pintype "passive"))
    )
    (net (code "28") (name "Net-(D1-BLU)") (class "Default")
      (node (ref "D1") (pin "1") (pinfunction "BLU_1") (pintype "bidirectional"))
      (node (ref "IC3") (pin "12") (pinfunction "SW1_12") (pintype "output"))
    )
    (net (code "29") (name "Net-(D1-GRN)") (class "Default")
      (node (ref "D1") (pin "3") (pinfunction "GRN_3") (pintype "bidirectional"))
      (node (ref "IC3") (pin "13") (pinfunction "SW2_13") (pintype "output"))
    )
    (net (code "30") (name "Net-(D1-RED)") (class "Default")
      (node (ref "D1") (pin "2") (pinfunction "RED_2") (pintype "bidirectional"))
      (node (ref "IC3") (pin "17") (pinfunction "SW5_17") (pintype "output"))
    )
    (net (code "31") (name "Net-(ENC1-3)") (class "Default")
      (node (ref "ENC1") (pin "1") (pinfunction "3_1") (pintype "passive"))
      (node (ref "SW1") (pin "B") (pinfunction "B_B") (pintype "passive"))
    )
    (net (code "32") (name "Net-(ENC2-3)") (class "Default")
      (node (ref "ENC2") (pin "1") (pinfunction "3_1") (pintype "passive"))
      (node (ref "SW1") (pin "A") (pinfunction "A_A") (pintype "passive"))
    )
    (net (code "33") (name "Net-(ENCBTN-3)") (class "Default")
      (node (ref "ENCBTN") (pin "1") (pinfunction "3_1") (pintype "passive"))
      (node (ref "SW1") (pin "P2") (pinfunction "2_P2") (pintype "passive"))
    )
    (net (code "34") (name "Net-(IC1A--IN)") (class "Default")
      (node (ref "IC1") (pin "2") (pinfunction "-IN_2") (pintype "input"))
      (node (ref "LED6") (pin "1") (pinfunction "1_1") (pintype "bidirectional"))
      (node (ref "R12") (pin "2") (pinfunction "2_2") (pintype "passive"))
    )
    (net (code "35") (name "Net-(IC1A-OUT)") (class "Default")
      (node (ref "IC1") (pin "1") (pinfunction "OUT_1") (pintype "output"))
      (node (ref "LED6") (pin "2") (pinfunction "2_2") (pintype "bidirectional"))
    )
    (net (code "36") (name "Net-(IC1B--IN)") (class "Default")
      (node (ref "IC1") (pin "6") (pinfunction "-IN_6") (pintype "input"))
      (node (ref "LED7") (pin "1") (pinfunction "1_1") (pintype "bidirectional"))
      (node (ref "R14") (pin "2") (pinfunction "2_2") (pintype "passive"))
    )
    (net (code "37") (name "Net-(IC1B-OUT)") (class "Default")
      (node (ref "IC1") (pin "7") (pinfunction "OUT_7") (pintype "output"))
      (node (ref "LED7") (pin "2") (pinfunction "2_2") (pintype "bidirectional"))
    )
    (net (code "38") (name "Net-(IC1C--IN)") (class "Default")
      (node (ref "IC1") (pin "9") (pinfunction "-IN_9") (pintype "input"))
      (node (ref "LED8") (pin "1") (pinfunction "1_1") (pintype "bidirectional"))
      (node (ref "R16") (pin "2") (pinfunction "2_2") (pintype "passive"))
    )
    (net (code "39") (name "Net-(IC1C-OUT)") (class "Default")
      (node (ref "IC1") (pin "8") (pinfunction "OUT_8") (pintype "output"))
      (node (ref "LED8") (pin "2") (pinfunction "2_2") (pintype "bidirectional"))
    )
    (net (code "40") (name "Net-(IC1D--IN)") (class "Default")
      (node (ref "IC1") (pin "13") (pinfunction "-IN_13") (pintype "input"))
      (node (ref "LED5") (pin "1") (pinfunction "1_1") (pintype "bidirectional"))
      (node (ref "R10") (pin "2") (pinfunction "2_2") (pintype "passive"))
    )
    (net (code "41") (name "Net-(IC1D-OUT)") (class "Default")
      (node (ref "IC1") (pin "14") (pinfunction "OUT_14") (pintype "output"))
      (node (ref "LED5") (pin "2") (pinfunction "2_2") (pintype "bidirectional"))
    )
    (net (code "42") (name "Net-(IC2A--IN)") (class "Default")
      (node (ref "IC2") (pin "2") (pinfunction "-IN_2") (pintype "input"))
      (node (ref "LED4") (pin "1") (pinfunction "1_1") (pintype "bidirectional"))
      (node (ref "R8") (pin "2") (pinfunction "2_2") (pintype "passive"))
    )
    (net (code "43") (name "Net-(IC2A-OUT)") (class "Default")
      (node (ref "IC2") (pin "1") (pinfunction "OUT_1") (pintype "output"))
      (node (ref "LED4") (pin "2") (pinfunction "2_2") (pintype "bidirectional"))
    )
    (net (code "44") (name "Net-(IC2B--IN)") (class "Default")
      (node (ref "IC2") (pin "6") (pinfunction "-IN_6") (pintype "input"))
      (node (ref "LED1") (pin "1") (pinfunction "1_1") (pintype "bidirectional"))
      (node (ref "R2") (pin "2") (pinfunction "2_2") (pintype "passive"))
    )
    (net (code "45") (name "Net-(IC2B-OUT)") (class "Default")
      (node (ref "IC2") (pin "7") (pinfunction "OUT_7") (pintype "output"))
      (node (ref "LED1") (pin "2") (pinfunction "2_2") (pintype "bidirectional"))
    )
    (net (code "46") (name "Net-(IC2C--IN)") (class "Default")
      (node (ref "IC2") (pin "9") (pinfunction "-IN_9") (pintype "input"))
      (node (ref "LED2") (pin "1") (pinfunction "1_1") (pintype "bidirectional"))
      (node (ref "R4") (pin "2") (pinfunction "2_2") (pintype "passive"))
    )
    (net (code "47") (name "Net-(IC2C-OUT)") (class "Default")
      (node (ref "IC2") (pin "8") (pinfunction "OUT_8") (pintype "output"))
      (node (ref "LED2") (pin "2") (pinfunction "2_2") (pintype "bidirectional"))
    )
    (net (code "48") (name "Net-(IC2D--IN)") (class "Default")
      (node (ref "IC2") (pin "13") (pinfunction "-IN_13") (pintype "input"))
      (node (ref "LED3") (pin "1") (pinfunction "1_1") (pintype "bidirectional"))
      (node (ref "R6") (pin "2") (pinfunction "2_2") (pintype "passive"))
    )
    (net (code "49") (name "Net-(IC2D-OUT)") (class "Default")
      (node (ref "IC2") (pin "14") (pinfunction "OUT_14") (pintype "output"))
      (node (ref "LED3") (pin "2") (pinfunction "2_2") (pintype "bidirectional"))
    )
    (net (code "50") (name "Net-(IC3-CS2)") (class "Default")
      (node (ref "IC3") (pin "21") (pinfunction "CS2_21") (pintype "output"))
      (node (ref "LED13") (pin "A") (pinfunction "A_A") (pintype "passive"))
      (node (ref "LED15") (pin "A") (pinfunction "A_A") (pintype "passive"))
    )
    (net (code "51") (name "Net-(IC3-CS3)") (class "Default")
      (node (ref "IC3") (pin "23") (pinfunction "CS3_23") (pintype "bidirectional"))
      (node (ref "LED12") (pin "A") (pinfunction "A_A") (pintype "passive"))
      (node (ref "LED14") (pin "A") (pinfunction "A_A") (pintype "passive"))
    )
    (net (code "52") (name "Net-(IC3-CS4)") (class "Default")
      (node (ref "IC3") (pin "24") (pinfunction "CS4_24") (pintype "bidirectional"))
      (node (ref "LED11") (pin "A") (pinfunction "A_A") (pintype "passive"))
      (node (ref "LED21") (pin "A") (pinfunction "A_A") (pintype "passive"))
    )
    (net (code "53") (name "Net-(IC3-CS5)") (class "Default")
      (node (ref "IC3") (pin "25") (pinfunction "CS5_25") (pintype "bidirectional"))
      (node (ref "LED10") (pin "A") (pinfunction "A_A") (pintype "passive"))
      (node (ref "LED22") (pin "A") (pinfunction "A_A") (pintype "passive"))
    )
    (net (code "54") (name "Net-(IC3-CS6)") (class "Default")
      (node (ref "IC3") (pin "26") (pinfunction "CS6_26") (pintype "bidirectional"))
      (node (ref "LED20") (pin "A") (pinfunction "A_A") (pintype "passive"))
      (node (ref "LED23") (pin "A") (pinfunction "A_A") (pintype "passive"))
    )
    (net (code "55") (name "Net-(IC3-CS7)") (class "Default")
      (node (ref "IC3") (pin "28") (pinfunction "CS7_28") (pintype "output"))
      (node (ref "LED19") (pin "A") (pinfunction "A_A") (pintype "passive"))
      (node (ref "LED24") (pin "A") (pinfunction "A_A") (pintype "passive"))
    )
    (net (code "56") (name "Net-(IC3-CS8)") (class "Default")
      (node (ref "IC3") (pin "1") (pinfunction "CS8_1") (pintype "output"))
      (node (ref "LED17") (pin "A") (pinfunction "A_A") (pintype "passive"))
      (node (ref "LED18") (pin "A") (pinfunction "A_A") (pintype "passive"))
    )
    (net (code "57") (name "Net-(IC3-R_EXT)") (class "Default")
      (node (ref "IC3") (pin "2") (pinfunction "R_EXT_2") (pintype "input"))
      (node (ref "R17") (pin "2") (pinfunction "2_2") (pintype "passive"))
    )
    (net (code "58") (name "Net-(IC3-SDB)") (class "Default")
      (node (ref "IC3") (pin "10") (pinfunction "SDB_10") (pintype "input"))
      (node (ref "R18") (pin "2") (pinfunction "2_2") (pintype "passive"))
    )
    (net (code "59") (name "Net-(IC3-SW3)") (class "Default")
      (node (ref "IC3") (pin "15") (pinfunction "SW3_15") (pintype "output"))
      (node (ref "LED10") (pin "C") (pinfunction "C_C") (pintype "passive"))
      (node (ref "LED11") (pin "C") (pinfunction "C_C") (pintype "passive"))
      (node (ref "LED12") (pin "C") (pinfunction "C_C") (pintype "passive"))
      (node (ref "LED13") (pin "C") (pinfunction "C_C") (pintype "passive"))
      (node (ref "LED18") (pin "C") (pinfunction "C_C") (pintype "passive"))
      (node (ref "LED19") (pin "C") (pinfunction "C_C") (pintype "passive"))
      (node (ref "LED20") (pin "C") (pinfunction "C_C") (pintype "passive"))
      (node (ref "LED9") (pin "C") (pinfunction "C_C") (pintype "passive"))
    )
    (net (code "60") (name "Net-(IC3-SW4)") (class "Default")
      (node (ref "IC3") (pin "16") (pinfunction "SW4_16") (pintype "output"))
      (node (ref "LED14") (pin "C") (pinfunction "C_C") (pintype "passive"))
      (node (ref "LED15") (pin "C") (pinfunction "C_C") (pintype "passive"))
      (node (ref "LED16") (pin "C") (pinfunction "C_C") (pintype "passive"))
      (node (ref "LED17") (pin "C") (pinfunction "C_C") (pintype "passive"))
      (node (ref "LED21") (pin "C") (pinfunction "C_C") (pintype "passive"))
      (node (ref "LED22") (pin "C") (pinfunction "C_C") (pintype "passive"))
      (node (ref "LED23") (pin "C") (pinfunction "C_C") (pintype "passive"))
      (node (ref "LED24") (pin "C") (pinfunction "C_C") (pintype "passive"))
    )
    (net (code "61") (name "Net-(OU1-2)") (class "Default")
      (node (ref "OU1") (pin "P$1") (pinfunction "2_P$1") (pintype "passive"))
      (node (ref "R1") (pin "2") (pinfunction "2_2") (pintype "passive"))
    )
    (net (code "62") (name "Net-(OUT2-2)") (class "Default")
      (node (ref "OUT2") (pin "P$1") (pinfunction "2_P$1") (pintype "passive"))
      (node (ref "R3") (pin "2") (pinfunction "2_2") (pintype "passive"))
    )
    (net (code "63") (name "Net-(OUT3-2)") (class "Default")
      (node (ref "OUT3") (pin "P$1") (pinfunction "2_P$1") (pintype "passive"))
      (node (ref "R5") (pin "2") (pinfunction "2_2") (pintype "passive"))
    )
    (net (code "64") (name "Net-(OUT4-2)") (class "Default")
      (node (ref "OUT4") (pin "P$1") (pinfunction "2_P$1") (pintype "passive"))
      (node (ref "R7") (pin "2") (pinfunction "2_2") (pintype "passive"))
    )
    (net (code "65") (name "Net-(OUT5-2)") (class "Default")
      (node (ref "OUT5") (pin "P$1") (pinfunction "2_P$1") (pintype "passive"))
      (node (ref "R9") (pin "2") (pinfunction "2_2") (pintype "passive"))
    )
    (net (code "66") (name "Net-(OUT6-2)") (class "Default")
      (node (ref "OUT6") (pin "P$1") (pinfunction "2_P$1") (pintype "passive"))
      (node (ref "R11") (pin "2") (pinfunction "2_2") (pintype "passive"))
    )
    (net (code "67") (name "Net-(OUT7-2)") (class "Default")
      (node (ref "OUT7") (pin "P$1") (pinfunction "2_P$1") (pintype "passive"))
      (node (ref "R13") (pin "2") (pinfunction "2_2") (pintype "passive"))
    )
    (net (code "68") (name "Net-(OUT8-2)") (class "Default")
      (node (ref "OUT8") (pin "P$1") (pinfunction "2_P$1") (pintype "passive"))
      (node (ref "R15") (pin "2") (pinfunction "2_2") (pintype "passive"))
    )
    (net (code "69") (name "Net-(TRIG_OUT-2)") (class "Default")
      (node (ref "R56") (pin "1") (pinfunction "1_1") (pintype "passive"))
      (node (ref "TRIG_OUT") (pin "P$1") (pinfunction "2_P$1") (pintype "passive"))
    )
    (net (code "70") (name "Net-(U1A-Y)") (class "Default")
      (node (ref "R56") (pin "2") (pinfunction "2_2") (pintype "passive"))
      (node (ref "U1") (pin "4") (pinfunction "Y_4") (pintype "tri_state"))
    )
    (net (code "71") (name "unconnected-(0_RX-3-Pad1)") (class "Default")
      (node (ref "0_RX") (pin "1") (pinfunction "3_1") (pintype "passive"))
    )
    (net (code "72") (name "unconnected-(1_TX-3-Pad1)") (class "Default")
      (node (ref "1_TX") (pin "1") (pinfunction "3_1") (pintype "passive"))
    )
    (net (code "73") (name "unconnected-(6-3-Pad1)") (class "Default")
      (node (ref "6") (pin "1") (pinfunction "3_1") (pintype "passive"))
    )
    (net (code "74") (name "unconnected-(7-3-Pad1)") (class "Default")
      (node (ref "7") (pin "1") (pinfunction "3_1") (pintype "passive"))
    )
    (net (code "75") (name "unconnected-(10_CS-3-Pad1)") (class "Default")
      (node (ref "10_CS") (pin "1") (pinfunction "3_1") (pintype "passive"))
    )
    (net (code "76") (name "unconnected-(11_MOSI-3-Pad1)") (class "Default")
      (node (ref "11_MOSI") (pin "1") (pinfunction "3_1") (pintype "passive"))
    )
    (net (code "77") (name "unconnected-(12_MISO-3-Pad1)") (class "Default")
      (node (ref "12_MISO") (pin "1") (pinfunction "3_1") (pintype "passive"))
    )
    (net (code "78") (name "unconnected-(13_SCK-3-Pad1)") (class "Default")
      (node (ref "13_SCK") (pin "1") (pinfunction "3_1") (pintype "passive"))
    )
    (net (code "79") (name "unconnected-(28-3-Pad1)") (class "Default")
      (node (ref "28") (pin "1") (pinfunction "3_1") (pintype "passive"))
    )
    (net (code "80") (name "unconnected-(29-3-Pad1)") (class "Default")
      (node (ref "29") (pin "1") (pinfunction "3_1") (pintype "passive"))
    )
    (net (code "81") (name "unconnected-(30-3-Pad1)") (class "Default")
      (node (ref "30") (pin "1") (pinfunction "3_1") (pintype "passive"))
    )
    (net (code "82") (name "unconnected-(31-3-Pad1)") (class "Default")
      (node (ref "31") (pin "1") (pinfunction "3_1") (pintype "passive"))
    )
    (net (code "83") (name "unconnected-(32-3-Pad1)") (class "Default")
      (node (ref "32") (pin "1") (pinfunction "3_1") (pintype "passive"))
    )
    (net (code "84") (name "unconnected-(33-3-Pad1)") (class "Default")
      (node (ref "33") (pin "1") (pinfunction "3_1") (pintype "passive"))
    )
    (net (code "85") (name "unconnected-(34-3-Pad1)") (class "Default")
      (node (ref "34") (pin "1") (pinfunction "3_1") (pintype "passive"))
    )
    (net (code "86") (name "unconnected-(35-3-Pad1)") (class "Default")
      (node (ref "35") (pin "1") (pinfunction "3_1") (pintype "passive"))
    )
    (net (code "87") (name "unconnected-(36-3-Pad1)") (class "Default")
      (node (ref "36") (pin "1") (pinfunction "3_1") (pintype "passive"))
    )
    (net (code "88") (name "unconnected-(37-3-Pad1)") (class "Default")
      (node (ref "37") (pin "1") (pinfunction "3_1") (pintype "passive"))
    )
    (net (code "89") (name "unconnected-(38-3-Pad1)") (class "Default")
      (node (ref "38") (pin "1") (pinfunction "3_1") (pintype "passive"))
    )
    (net (code "90") (name "unconnected-(39-3-Pad1)") (class "Default")
      (node (ref "39") (pin "1") (pinfunction "3_1") (pintype "passive"))
    )
    (net (code "91") (name "unconnected-(40-3-Pad1)") (class "Default")
      (node (ref "40") (pin "1") (pinfunction "3_1") (pintype "passive"))
    )
    (net (code "92") (name "unconnected-(41-3-Pad1)") (class "Default")
      (node (ref "41") (pin "1") (pinfunction "3_1") (pintype "passive"))
    )
    (net (code "93") (name "unconnected-(CV1_-3-Pad1)") (class "Default")
      (node (ref "CV1_") (pin "1") (pinfunction "3_1") (pintype "passive"))
    )
    (net (code "94") (name "unconnected-(CV6-3-Pad1)") (class "Default")
      (node (ref "CV6") (pin "1") (pinfunction "3_1") (pintype "passive"))
    )
    (net (code "95") (name "unconnected-(CV6_-3-Pad1)") (class "Default")
      (node (ref "CV6_") (pin "1") (pinfunction "3_1") (pintype "passive"))
    )
    (net (code "96") (name "unconnected-(CV7-3-Pad1)") (class "Default")
      (node (ref "CV7") (pin "1") (pinfunction "3_1") (pintype "passive"))
    )
    (net (code "97") (name "unconnected-(CV7_-3-Pad1)") (class "Default")
      (node (ref "CV7_") (pin "1") (pinfunction "3_1") (pintype "passive"))
    )
    (net (code "98") (name "unconnected-(CV8-3-Pad1)") (class "Default")
      (node (ref "CV8") (pin "1") (pinfunction "3_1") (pintype "passive"))
    )
    (net (code "99") (name "unconnected-(CV8_-3-Pad1)") (class "Default")
      (node (ref "CV8_") (pin "1") (pinfunction "3_1") (pintype "passive"))
    )
    (net (code "100") (name "unconnected-(CV9-3-Pad1)") (class "Default")
      (node (ref "CV9") (pin "1") (pinfunction "3_1") (pintype "passive"))
    )
    (net (code "101") (name "unconnected-(CV9_-3-Pad1)") (class "Default")
      (node (ref "CV9_") (pin "1") (pinfunction "3_1") (pintype "passive"))
    )
    (net (code "102") (name "unconnected-(CV10-3-Pad1)") (class "Default")
      (node (ref "CV10") (pin "1") (pinfunction "3_1") (pintype "passive"))
    )
    (net (code "103") (name "unconnected-(CV10_-3-Pad1)") (class "Default")
      (node (ref "CV10_") (pin "1") (pinfunction "3_1") (pintype "passive"))
    )
    (net (code "104") (name "unconnected-(CV11-3-Pad1)") (class "Default")
      (node (ref "CV11") (pin "1") (pinfunction "3_1") (pintype "passive"))
    )
    (net (code "105") (name "unconnected-(CV11_-3-Pad1)") (class "Default")
      (node (ref "CV11_") (pin "1") (pinfunction "3_1") (pintype "passive"))
    )
    (net (code "106") (name "unconnected-(CV12-3-Pad1)") (class "Default")
      (node (ref "CV12") (pin "1") (pinfunction "3_1") (pintype "passive"))
    )
    (net (code "107") (name "unconnected-(CV12_-3-Pad1)") (class "Default")
      (node (ref "CV12_") (pin "1") (pinfunction "3_1") (pintype "passive"))
    )
    (net (code "108") (name "unconnected-(IC3-INTB-Pad9)") (class "Default")
      (node (ref "IC3") (pin "9") (pinfunction "INTB_9") (pintype "input"))
    )
    (net (code "109") (name "unconnected-(IC3-SW6-Pad19)") (class "Default")
      (node (ref "IC3") (pin "19") (pinfunction "SW6_19") (pintype "output"))
    )
    (net (code "110") (name "unconnected-(IC3-SYNC-Pad5)") (class "Default")
      (node (ref "IC3") (pin "5") (pinfunction "SYNC_5") (pintype "input"))
    )
    (net (code "111") (name "unconnected-(IO1-3-Pad1)") (class "Default")
      (node (ref "IO1") (pin "1") (pinfunction "3_1") (pintype "passive"))
    )
    (net (code "112") (name "unconnected-(IO2-3-Pad1)") (class "Default")
      (node (ref "IO2") (pin "1") (pinfunction "3_1") (pintype "passive"))
    )
    (net (code "113") (name "unconnected-(IO3-3-Pad1)") (class "Default")
      (node (ref "IO3") (pin "1") (pinfunction "3_1") (pintype "passive"))
    )
    (net (code "114") (name "unconnected-(IO4-3-Pad1)") (class "Default")
      (node (ref "IO4") (pin "1") (pinfunction "3_1") (pintype "passive"))
    )
    (net (code "115") (name "unconnected-(IO5-3-Pad1)") (class "Default")
      (node (ref "IO5") (pin "1") (pinfunction "3_1") (pintype "passive"))
    )
    (net (code "116") (name "unconnected-(IO6-3-Pad1)") (class "Default")
      (node (ref "IO6") (pin "1") (pinfunction "3_1") (pintype "passive"))
    )
    (net (code "117") (name "unconnected-(IO7-3-Pad1)") (class "Default")
      (node (ref "IO7") (pin "1") (pinfunction "3_1") (pintype "passive"))
    )
    (net (code "118") (name "unconnected-(IO8-3-Pad1)") (class "Default")
      (node (ref "IO8") (pin "1") (pinfunction "3_1") (pintype "passive"))
    )
    (net (code "119") (name "unconnected-(IO9-3-Pad1)") (class "Default")
      (node (ref "IO9") (pin "1") (pinfunction "3_1") (pintype "passive"))
    )
    (net (code "120") (name "unconnected-(IO10-3-Pad1)") (class "Default")
      (node (ref "IO10") (pin "1") (pinfunction "3_1") (pintype "passive"))
    )
    (net (code "121") (name "unconnected-(IO11-3-Pad1)") (class "Default")
      (node (ref "IO11") (pin "1") (pinfunction "3_1") (pintype "passive"))
    )
    (net (code "122") (name "unconnected-(IO12-3-Pad1)") (class "Default")
      (node (ref "IO12") (pin "1") (pinfunction "3_1") (pintype "passive"))
    )
    (net (code "123") (name "unconnected-(IO13-3-Pad1)") (class "Default")
      (node (ref "IO13") (pin "1") (pinfunction "3_1") (pintype "passive"))
    )
    (net (code "124") (name "unconnected-(IO14-3-Pad1)") (class "Default")
      (node (ref "IO14") (pin "1") (pinfunction "3_1") (pintype "passive"))
    )
    (net (code "125") (name "unconnected-(IO15-3-Pad1)") (class "Default")
      (node (ref "IO15") (pin "1") (pinfunction "3_1") (pintype "passive"))
    )
    (net (code "126") (name "unconnected-(IO16-3-Pad1)") (class "Default")
      (node (ref "IO16") (pin "1") (pinfunction "3_1") (pintype "passive"))
    )
    (net (code "127") (name "unconnected-(OU1-3-PadP$2)") (class "Default")
      (node (ref "OU1") (pin "P$2") (pinfunction "3_P$2") (pintype "passive"))
    )
    (net (code "128") (name "unconnected-(OUT2-3-PadP$2)") (class "Default")
      (node (ref "OUT2") (pin "P$2") (pinfunction "3_P$2") (pintype "passive"))
    )
    (net (code "129") (name "unconnected-(OUT3-3-PadP$2)") (class "Default")
      (node (ref "OUT3") (pin "P$2") (pinfunction "3_P$2") (pintype "passive"))
    )
    (net (code "130") (name "unconnected-(OUT4-3-PadP$2)") (class "Default")
      (node (ref "OUT4") (pin "P$2") (pinfunction "3_P$2") (pintype "passive"))
    )
    (net (code "131") (name "unconnected-(OUT5-3-PadP$2)") (class "Default")
      (node (ref "OUT5") (pin "P$2") (pinfunction "3_P$2") (pintype "passive"))
    )
    (net (code "132") (name "unconnected-(OUT6-3-PadP$2)") (class "Default")
      (node (ref "OUT6") (pin "P$2") (pinfunction "3_P$2") (pintype "passive"))
    )
    (net (code "133") (name "unconnected-(OUT7-3-PadP$2)") (class "Default")
      (node (ref "OUT7") (pin "P$2") (pinfunction "3_P$2") (pintype "passive"))
    )
    (net (code "134") (name "unconnected-(OUT8-3-PadP$2)") (class "Default")
      (node (ref "OUT8") (pin "P$2") (pinfunction "3_P$2") (pintype "passive"))
    )
    (net (code "135") (name "unconnected-(TRIG_OUT-3-PadP$2)") (class "Default")
      (node (ref "TRIG_OUT") (pin "P$2") (pinfunction "3_P$2") (pintype "passive"))
    )
  )
)
